# Sheet1.net
KiCad netlist of a schematic drawn in Altium Designer
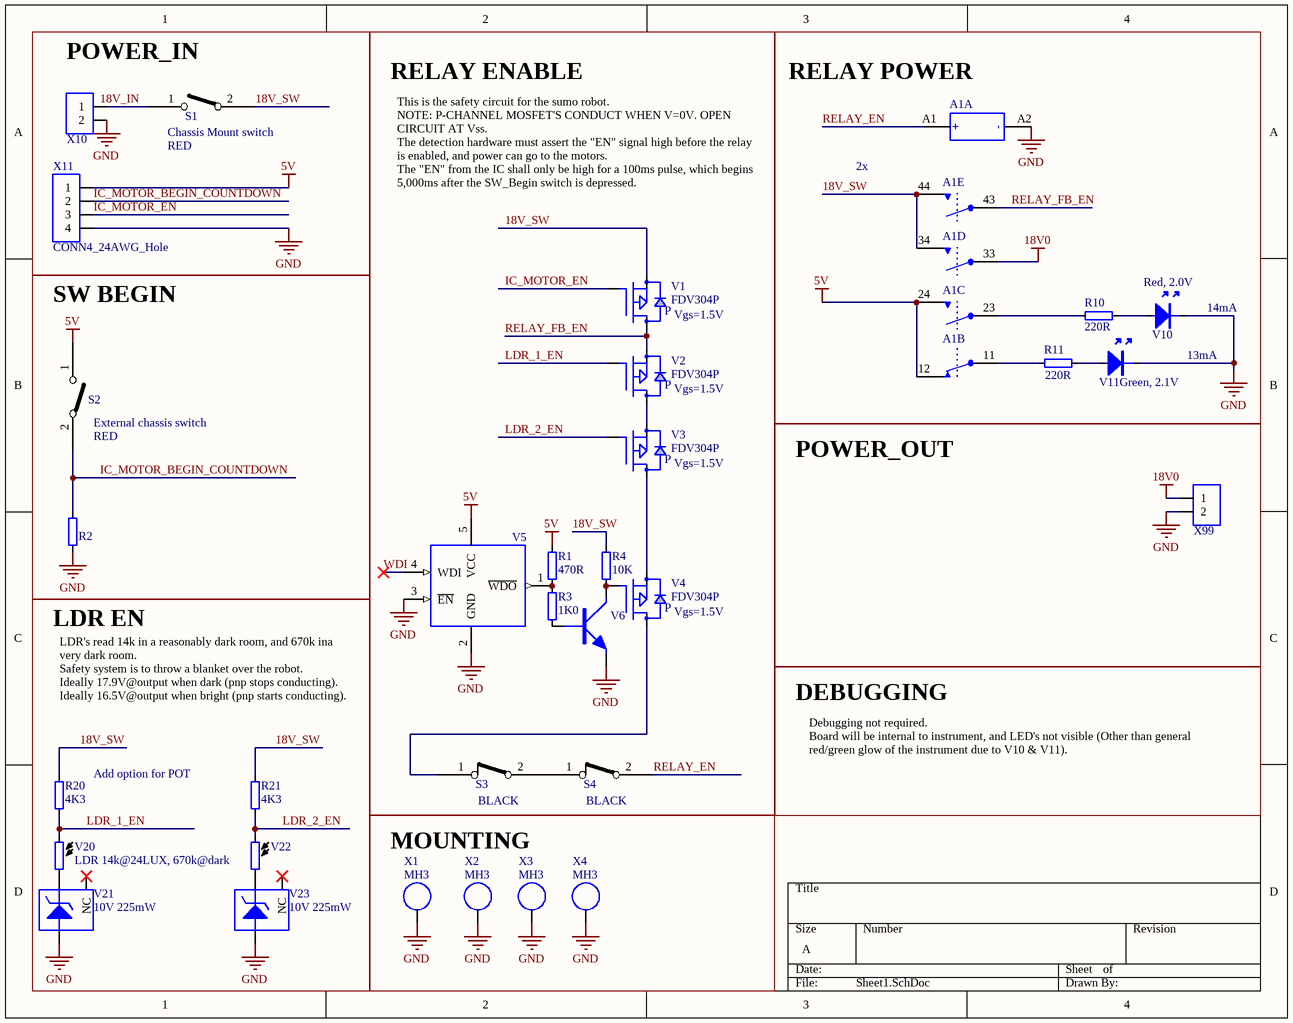
[diagram p0: Sheet1.SchDoc]

(export (version "E")
  (design (tool "Eeschema 10.0.6"))
  (components
    (comp (ref "A1")
      (value "RELAY SAFETY 4PST 8A 18V")
      (footprint "RELAY-BRUMFIELD-4PST-3NO-1NC")
      (description "Safety Relay 4PST, 3NO 1 NC")
      (fields
        (field (name "MANUFACTURER") "TE Connectivity Potter & Brumfield Relays")
        (field (name "PARTNUMBER") "SR4M4018")
      )
      (libsource (lib "SVN_BOMGEN_Database_2014") (part "RELAY-4PST-3A1B"))
    )
    (comp (ref "R1")
      (value "470R")
      (footprint "1206")
      (description "Resistor")
      (fields
        (field (name "MANUFACTURER") "Phycomp")
        (field (name "PARTNUMBER") "RC1206FR-07470RL")
        (field (name "CHECKEDBY") "ART")
      )
      (libsource (lib "SVN_BOMGEN_Database_2014") (part "RES"))
    )
    (comp (ref "R2")
      (value "10K")
      (footprint "1206")
      (description "Resistor")
      (fields
        (field (name "MANUFACTURER") "Phycomp")
        (field (name "PARTNUMBER") "RC1206FR-0710KL")
        (field (name "CHECKEDBY") "ART")
      )
      (libsource (lib "SVN_BOMGEN_Database_2014") (part "RES"))
    )
    (comp (ref "R3")
      (value "1K0")
      (footprint "1206")
      (description "Resistor")
      (fields
        (field (name "MANUFACTURER") "Phycomp")
        (field (name "PARTNUMBER") "RC1206FR-071KL")
        (field (name "CHECKEDBY") "ART")
      )
      (libsource (lib "SVN_BOMGEN_Database_2014") (part "RES"))
    )
    (comp (ref "R4")
      (value "10K")
      (footprint "1206")
      (description "Resistor")
      (fields
        (field (name "MANUFACTURER") "Phycomp")
        (field (name "PARTNUMBER") "RC1206FR-0710KL")
        (field (name "CHECKEDBY") "ART")
      )
      (libsource (lib "SVN_BOMGEN_Database_2014") (part "RES"))
    )
    (comp (ref "R10")
      (value "220R")
      (footprint "1206")
      (description "Resistor")
      (fields
        (field (name "MANUFACTURER") "Phycomp")
        (field (name "PARTNUMBER") "RC1206FR-07220RL")
        (field (name "CHECKEDBY") "ART")
      )
      (libsource (lib "SVN_BOMGEN_Database_2014") (part "RES"))
    )
    (comp (ref "R11")
      (value "220R")
      (footprint "1206")
      (description "Resistor")
      (fields
        (field (name "MANUFACTURER") "Phycomp")
        (field (name "PARTNUMBER") "RC1206FR-07220RL")
        (field (name "CHECKEDBY") "ART")
      )
      (libsource (lib "SVN_BOMGEN_Database_2014") (part "RES"))
    )
    (comp (ref "R20")
      (value "4K3")
      (footprint "0603")
      (description "Resistor")
      (fields
        (field (name "MANUFACTURER") "Phycomp")
        (field (name "PARTNUMBER") "RC0603FR-074K3L")
        (field (name "CHECKEDBY") "ART")
      )
      (libsource (lib "SVN_BOMGEN_Database_2014") (part "RES"))
    )
    (comp (ref "R21")
      (value "4K3")
      (footprint "0603")
      (description "Resistor")
      (fields
        (field (name "MANUFACTURER") "Phycomp")
        (field (name "PARTNUMBER") "RC0603FR-074K3L")
        (field (name "CHECKEDBY") "ART")
      )
      (libsource (lib "SVN_BOMGEN_Database_2014") (part "RES"))
    )
    (comp (ref "S1")
      (value "SWITCH Rocker SPST Panel Mount, Red")
      (footprint "2_Wire_12AWG")
      (description "SWITCH")
      (fields (field (name "MANUFACTURER") "Cherry") (field (name "PARTNUMBER") "CRE22F2BBRLE"))
      (libsource (lib "SVN_BOMGEN_Database_2014") (part "Switch_SPST-NO"))
    )
    (comp (ref "S2")
      (value "Switch NO")
      (footprint "2_Wire_12AWG")
      (description "SWITCH")
      (fields (field (name "MANUFACTURER") "TE Connectivity") (field (name "PARTNUMBER") "1437568-6"))
      (libsource (lib "SVN_BOMGEN_Database_2014") (part "Switch_SPST-NO"))
    )
    (comp (ref "S3")
      (value "Switch NC")
      (footprint "2_Wire_20AWG")
      (description "SWITCH")
      (fields (field (name "MANUFACTURER") "TE Connectivity") (field (name "PARTNUMBER") "MSPS103B"))
      (libsource (lib "SVN_BOMGEN_Database_2014") (part "Switch_SPST-NC"))
    )
    (comp (ref "S4")
      (value "Switch NC")
      (footprint "2_Wire_20AWG")
      (description "SWITCH")
      (fields (field (name "MANUFACTURER") "TE Connectivity") (field (name "PARTNUMBER") "MSPS103B"))
      (libsource (lib "SVN_BOMGEN_Database_2014") (part "Switch_SPST-NC"))
    )
    (comp (ref "V1")
      (value "FDV304P")
      (footprint "SOT23")
      (description "MOSFET P CHANNEL GENERIC SOT23")
      (fields (field (name "MANUFACTURER") "Fairchild") (field (name "CHECKEDBY") "AJR"))
      (libsource (lib "SVN_BOMGEN_Database_2014") (part "MOSFET-P-SOT23"))
    )
    (comp (ref "V2")
      (value "FDV304P")
      (footprint "SOT23")
      (description "MOSFET P CHANNEL GENERIC SOT23")
      (fields (field (name "MANUFACTURER") "Fairchild") (field (name "CHECKEDBY") "AJR"))
      (libsource (lib "SVN_BOMGEN_Database_2014") (part "MOSFET-P-SOT23"))
    )
    (comp (ref "V3")
      (value "FDV304P")
      (footprint "SOT23")
      (description "MOSFET P CHANNEL GENERIC SOT23")
      (fields (field (name "MANUFACTURER") "Fairchild") (field (name "CHECKEDBY") "AJR"))
      (libsource (lib "SVN_BOMGEN_Database_2014") (part "MOSFET-P-SOT23"))
    )
    (comp (ref "V4")
      (value "FDV304P")
      (footprint "SOT23")
      (description "MOSFET P CHANNEL GENERIC SOT23")
      (fields (field (name "MANUFACTURER") "Fairchild") (field (name "CHECKEDBY") "AJR"))
      (libsource (lib "SVN_BOMGEN_Database_2014") (part "MOSFET-P-SOT23"))
    )
    (comp (ref "V5")
      (value "STWD100NYWY3F")
      (footprint "SOT23-5")
      (description "IC Watchdog Timer Circuit")
      (fields (field (name "MANUFACTURER") "ST Microelectronics") (field (name "CHECKEDBY") "SAA"))
      (libsource (lib "SVN_BOMGEN_Database_2014") (part "STWD100"))
    )
    (comp (ref "V6")
      (value "BC846B")
      (footprint "SOT23")
      (description "NPN Transistor SOT23")
      (fields (field (name "MANUFACTURER") "NXP") (field (name "CHECKEDBY") "LZZ"))
      (libsource (lib "SVN_BOMGEN_Database_2014") (part "NPN-SOT23"))
    )
    (comp (ref "V10")
      (value "Red, 2.0V")
      (footprint "LED-0805")
      (description "LED")
      (fields
        (field (name "MANUFACTURER") "Kingbright")
        (field (name "PARTNUMBER") "KP-2012EC")
        (field (name "CHECKEDBY") "ART")
      )
      (libsource (lib "SVN_BOMGEN_Database_2014") (part "LED"))
    )
    (comp (ref "V11")
      (value "Green, 2.1V")
      (footprint "LED-0805")
      (description "LED")
      (fields
        (field (name "MANUFACTURER") "Chicago Miniature Lighting")
        (field (name "PARTNUMBER") "CMD17-21UGC/TR8")
        (field (name "CHECKEDBY") "SAA")
      )
      (libsource (lib "SVN_BOMGEN_Database_2014") (part "LED"))
    )
    (comp (ref "V20")
      (value "LDR 14k@24LUX, 670k@dark")
      (footprint "LDR_NSL-5112")
      (description "LDR")
      (fields (field (name "MANUFACTURER") "Luna Optoelectronics") (field (name "PARTNUMBER") "NSL-5112"))
      (libsource (lib "SVN_BOMGEN_Database_2014") (part "LDR"))
    )
    (comp (ref "V21")
      (value "10V 225mW")
      (footprint "SOT23")
      (description "DIODE ZENER SOT23 a-z k-x nc-y")
      (fields (field (name "MANUFACTURER") "ON Semi") (field (name "PARTNUMBER") "BZX84C10LT1G"))
      (libsource (lib "SVN_BOMGEN_Database_2014") (part "ZENER-SOT23"))
    )
    (comp (ref "V22")
      (value "LDR 14k@24LUX, 670k@dark")
      (footprint "LDR_NSL-5112")
      (description "LDR")
      (fields (field (name "MANUFACTURER") "Luna Optoelectronics") (field (name "PARTNUMBER") "NSL-5112"))
      (libsource (lib "SVN_BOMGEN_Database_2014") (part "LDR"))
    )
    (comp (ref "V23")
      (value "10V 225mW")
      (footprint "SOT23")
      (description "DIODE ZENER SOT23 a-z k-x nc-y")
      (fields (field (name "MANUFACTURER") "ON Semi") (field (name "PARTNUMBER") "BZX84C10LT1G"))
      (libsource (lib "SVN_BOMGEN_Database_2014") (part "ZENER-SOT23"))
    )
    (comp (ref "X1")
      (value "MH3")
      (footprint "MH-M3-SEMS-6.7-3.6-Vias-Unplated")
      (description "MOUNTING HOLE")
      (fields (field (name "CHECKEDBY") "vhq"))
      (libsource (lib "SVN_BOMGEN_Database_2014") (part "MOUNTING-HOLE"))
    )
    (comp (ref "X2")
      (value "MH3")
      (footprint "MH-M3-SEMS-6.7-3.6-Vias-Unplated")
      (description "MOUNTING HOLE")
      (fields (field (name "CHECKEDBY") "vhq"))
      (libsource (lib "SVN_BOMGEN_Database_2014") (part "MOUNTING-HOLE"))
    )
    (comp (ref "X3")
      (value "MH3")
      (footprint "MH-M3-SEMS-6.7-3.6-Vias-Unplated")
      (description "MOUNTING HOLE")
      (fields (field (name "CHECKEDBY") "vhq"))
      (libsource (lib "SVN_BOMGEN_Database_2014") (part "MOUNTING-HOLE"))
    )
    (comp (ref "X4")
      (value "MH3")
      (footprint "MH-M3-SEMS-6.7-3.6-Vias-Unplated")
      (description "MOUNTING HOLE")
      (fields (field (name "CHECKEDBY") "vhq"))
      (libsource (lib "SVN_BOMGEN_Database_2014") (part "MOUNTING-HOLE"))
    )
    (comp (ref "X10")
      (value "CONN2_12AWG_Hole")
      (footprint "2_Wire_12AWG")
      (fields (field (name "CHECKEDBY") "-"))
      (libsource (lib "") (part "CONN2_12AWG_Hole_1"))
    )
    (comp (ref "X11")
      (value "CONN4_24AWG_Hole")
      (footprint "4_Wire_0.1\"")
      (libsource (lib "Sumo_2016") (part "CONN4"))
    )
    (comp (ref "X99")
      (value "CONN2_12AWG_Hole")
      (footprint "2_Wire_12AWG")
      (fields (field (name "CHECKEDBY") "-"))
      (libsource (lib "Sumo_2016") (part "CONN2_12AWG_Hole"))
    )
  )
  (nets
    (net (code "2") (name "/18V_SW") (class "Default")
      (node (ref "A1") (pin "34") (pinfunction "34_34") (pintype "passive"))
      (node (ref "A1") (pin "44") (pinfunction "44_44") (pintype "passive"))
      (node (ref "R20") (pin "2") (pinfunction "2_2") (pintype "passive"))
      (node (ref "R21") (pin "2") (pinfunction "2_2") (pintype "passive"))
      (node (ref "R4") (pin "2") (pinfunction "2_2") (pintype "passive"))
      (node (ref "S1") (pin "2") (pinfunction "2_2") (pintype "passive"))
      (node (ref "V1") (pin "y") (pinfunction "s_y") (pintype "passive"))
    )
    (net (code "3") (name "/IC_MOTOR_BEGIN_COUNTDOWN") (class "Default")
      (node (ref "R2") (pin "2") (pinfunction "2_2") (pintype "passive"))
      (node (ref "S2") (pin "2") (pinfunction "2_2") (pintype "passive"))
      (node (ref "X11") (pin "2") (pinfunction "2_2") (pintype "passive"))
    )
    (net (code "4") (name "/IC_MOTOR_EN") (class "Default")
      (node (ref "V1") (pin "z") (pinfunction "gate_z") (pintype "passive"))
      (node (ref "X11") (pin "3") (pinfunction "3_3") (pintype "passive"))
    )
    (net (code "5") (name "/LDR_1_EN") (class "Default")
      (node (ref "R20") (pin "1") (pinfunction "1_1") (pintype "passive"))
      (node (ref "V2") (pin "z") (pinfunction "gate_z") (pintype "passive"))
      (node (ref "V20") (pin "1") (pinfunction "1_1") (pintype "passive"))
    )
    (net (code "6") (name "/LDR_2_EN") (class "Default")
      (node (ref "R21") (pin "1") (pinfunction "1_1") (pintype "passive"))
      (node (ref "V22") (pin "1") (pinfunction "1_1") (pintype "passive"))
      (node (ref "V3") (pin "z") (pinfunction "gate_z") (pintype "passive"))
    )
    (net (code "7") (name "/RELAY_EN") (class "Default")
      (node (ref "A1") (pin "A1") (pinfunction "A1_A1") (pintype "passive"))
      (node (ref "S4") (pin "2") (pinfunction "2_2") (pintype "passive"))
    )
    (net (code "8") (name "/RELAY_FB_EN") (class "Default")
      (node (ref "A1") (pin "43") (pinfunction "43_43") (pintype "passive"))
      (node (ref "V1") (pin "x") (pinfunction "d_x") (pintype "passive"))
      (node (ref "V2") (pin "y") (pinfunction "s_y") (pintype "passive"))
    )
    (net (code "9") (name "/WDI") (class "Default")
      (node (ref "V5") (pin "4") (pinfunction "WDI_4") (pintype "input+no_connect"))
    )
    (net (code "10") (name "5V") (class "Default")
      (node (ref "A1") (pin "12") (pinfunction "12_12") (pintype "passive"))
      (node (ref "A1") (pin "24") (pinfunction "24_24") (pintype "passive"))
      (node (ref "R1") (pin "1") (pinfunction "1_1") (pintype "passive"))
      (node (ref "S2") (pin "1") (pinfunction "1_1") (pintype "passive"))
      (node (ref "V5") (pin "5") (pinfunction "VCC_5") (pintype "power_in"))
      (node (ref "X11") (pin "1") (pinfunction "1_1") (pintype "passive"))
    )
    (net (code "11") (name "18V0") (class "Default")
      (node (ref "A1") (pin "33") (pinfunction "33_33") (pintype "passive"))
      (node (ref "X99") (pin "1") (pinfunction "1_1") (pintype "passive"))
    )
    (net (code "12") (name "GND") (class "Default")
      (node (ref "A1") (pin "A2") (pinfunction "A2_A2") (pintype "passive"))
      (node (ref "R2") (pin "1") (pinfunction "1_1") (pintype "passive"))
      (node (ref "V10") (pin "k") (pintype "passive"))
      (node (ref "V11") (pin "k") (pintype "passive"))
      (node (ref "V21") (pin "z") (pinfunction "a_z") (pintype "passive"))
      (node (ref "V23") (pin "z") (pinfunction "a_z") (pintype "passive"))
      (node (ref "V5") (pin "2") (pinfunction "GND_2") (pintype "power_in"))
      (node (ref "V5") (pin "3") (pinfunction "~{EN}_3") (pintype "input"))
      (node (ref "V6") (pin "y") (pinfunction "Emitter_y") (pintype "passive"))
      (node (ref "X1") (pin "1") (pinfunction "1_1") (pintype "passive"))
      (node (ref "X10") (pin "2") (pinfunction "2_2") (pintype "passive"))
      (node (ref "X11") (pin "4") (pinfunction "4_4") (pintype "passive"))
      (node (ref "X2") (pin "1") (pinfunction "1_1") (pintype "passive"))
      (node (ref "X3") (pin "1") (pinfunction "1_1") (pintype "passive"))
      (node (ref "X4") (pin "1") (pinfunction "1_1") (pintype "passive"))
      (node (ref "X99") (pin "2") (pinfunction "2_2") (pintype "passive"))
    )
    (net (code "13") (name "Net-(A1-Pad11)") (class "Default")
      (node (ref "A1") (pin "11") (pinfunction "11_11") (pintype "passive"))
      (node (ref "R11") (pin "1") (pinfunction "1_1") (pintype "passive"))
    )
    (net (code "14") (name "Net-(A1-Pad23)") (class "Default")
      (node (ref "A1") (pin "23") (pinfunction "23_23") (pintype "passive"))
      (node (ref "R10") (pin "1") (pinfunction "1_1") (pintype "passive"))
    )
    (net (code "15") (name "Net-(R10-Pad2)") (class "Default")
      (node (ref "R10") (pin "2") (pinfunction "2_2") (pintype "passive"))
      (node (ref "V10") (pin "a") (pintype "passive"))
    )
    (net (code "16") (name "Net-(R11-Pad2)") (class "Default")
      (node (ref "R11") (pin "2") (pinfunction "2_2") (pintype "passive"))
      (node (ref "V11") (pin "a") (pintype "passive"))
    )
    (net (code "17") (name "Net-(S1-Pad1)") (class "Default")
      (node (ref "S1") (pin "1") (pinfunction "1_1") (pintype "passive"))
      (node (ref "X10") (pin "1") (pinfunction "1_1") (pintype "passive"))
    )
    (net (code "18") (name "Net-(S3-Pad2)") (class "Default")
      (node (ref "S3") (pin "2") (pinfunction "2_2") (pintype "passive"))
      (node (ref "S4") (pin "1") (pinfunction "1_1") (pintype "passive"))
    )
    (net (code "19") (name "Net-(V2-d)") (class "Default")
      (node (ref "V2") (pin "x") (pinfunction "d_x") (pintype "passive"))
      (node (ref "V3") (pin "y") (pinfunction "s_y") (pintype "passive"))
    )
    (net (code "20") (name "Net-(V3-d)") (class "Default")
      (node (ref "V3") (pin "x") (pinfunction "d_x") (pintype "passive"))
      (node (ref "V4") (pin "y") (pinfunction "s_y") (pintype "passive"))
    )
    (net (code "21") (name "Net-(V4-d)") (class "Default")
      (node (ref "S3") (pin "1") (pinfunction "1_1") (pintype "passive"))
      (node (ref "V4") (pin "x") (pinfunction "d_x") (pintype "passive"))
    )
    (net (code "22") (name "Net-(V4-gate)") (class "Default")
      (node (ref "R4") (pin "1") (pinfunction "1_1") (pintype "passive"))
      (node (ref "V4") (pin "z") (pinfunction "gate_z") (pintype "passive"))
      (node (ref "V6") (pin "x") (pinfunction "Collector_x") (pintype "passive"))
    )
    (net (code "23") (name "Net-(V5-~{WDO})") (class "Default")
      (node (ref "R1") (pin "2") (pinfunction "2_2") (pintype "passive"))
      (node (ref "R3") (pin "2") (pinfunction "2_2") (pintype "passive"))
      (node (ref "V5") (pin "1") (pinfunction "~{WDO}_1") (pintype "output"))
    )
    (net (code "24") (name "Net-(V6-Base)") (class "Default")
      (node (ref "R3") (pin "1") (pinfunction "1_1") (pintype "passive"))
      (node (ref "V6") (pin "z") (pinfunction "Base_z") (pintype "passive"))
    )
    (net (code "25") (name "Net-(V21-k)") (class "Default")
      (node (ref "V20") (pin "2") (pinfunction "2_2") (pintype "passive"))
      (node (ref "V21") (pin "x") (pinfunction "k_x") (pintype "passive"))
    )
    (net (code "26") (name "Net-(V23-k)") (class "Default")
      (node (ref "V22") (pin "2") (pinfunction "2_2") (pintype "passive"))
      (node (ref "V23") (pin "x") (pinfunction "k_x") (pintype "passive"))
    )
    (net (code "27") (name "unconnected-(V21-NC-Pady)") (class "Default")
      (node (ref "V21") (pin "y") (pinfunction "NC_y") (pintype "passive+no_connect"))
    )
    (net (code "28") (name "unconnected-(V23-NC-Pady)") (class "Default")
      (node (ref "V23") (pin "y") (pinfunction "NC_y") (pintype "passive+no_connect"))
    )
  )
)
